# rx.net
KiCad netlist of a schematic drawn in EAGLE
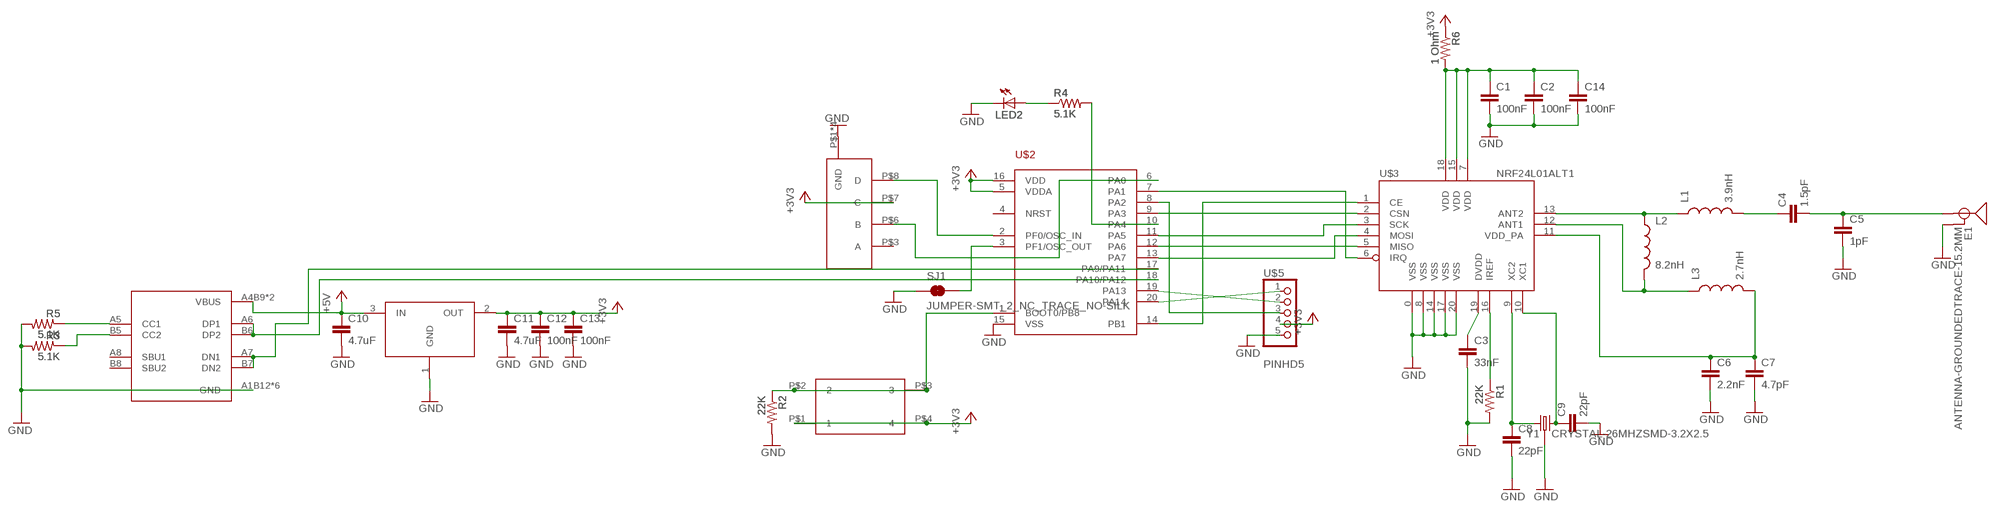
[diagram p0: schematic, sheet 1]

(export (version "E")
  (design (tool "Eeschema 10.0.6"))
  (components
    (comp (ref "C1")
      (value "100nF")
      (footprint "eagle-import:0805")
      (libsource (lib "eagle-import") (part "CAP0805"))
    )
    (comp (ref "C2")
      (value "100nF")
      (footprint "eagle-import:0805")
      (libsource (lib "eagle-import") (part "CAP0805"))
    )
    (comp (ref "C3")
      (value "33nF")
      (footprint "eagle-import:0805")
      (libsource (lib "eagle-import") (part "CAP0805"))
    )
    (comp (ref "C4")
      (value "1.5pF")
      (footprint "eagle-import:0805")
      (libsource (lib "eagle-import") (part "CAP0805"))
    )
    (comp (ref "C5")
      (value "1pF")
      (footprint "eagle-import:0805")
      (libsource (lib "eagle-import") (part "CAP0805"))
    )
    (comp (ref "C6")
      (value "2.2nF")
      (footprint "eagle-import:0805")
      (libsource (lib "eagle-import") (part "CAP0805"))
    )
    (comp (ref "C7")
      (value "4.7pF")
      (footprint "eagle-import:0805")
      (libsource (lib "eagle-import") (part "CAP0805"))
    )
    (comp (ref "C8")
      (value "22pF")
      (footprint "eagle-import:0805")
      (libsource (lib "eagle-import") (part "CAP0805"))
    )
    (comp (ref "C9")
      (value "22pF")
      (footprint "eagle-import:0805")
      (libsource (lib "eagle-import") (part "CAP0805"))
    )
    (comp (ref "C10")
      (value "4.7uF")
      (footprint "eagle-import:0805")
      (libsource (lib "eagle-import") (part "CAP0805"))
    )
    (comp (ref "C11")
      (value "4.7uF")
      (footprint "eagle-import:0805")
      (libsource (lib "eagle-import") (part "CAP0805"))
    )
    (comp (ref "C12")
      (value "100nF")
      (footprint "eagle-import:0805")
      (libsource (lib "eagle-import") (part "CAP0805"))
    )
    (comp (ref "C13")
      (value "100nF")
      (footprint "eagle-import:0805")
      (libsource (lib "eagle-import") (part "CAP0805"))
    )
    (comp (ref "C14")
      (value "100nF")
      (footprint "eagle-import:0805")
      (libsource (lib "eagle-import") (part "CAP0805"))
    )
    (comp (ref "E1")
      (value "ANTENNA-GROUNDEDTRACE-15.2MM")
      (footprint "eagle-import:TRACE_ANTENNA_2.4GHZ_15.2MM")
      (libsource (lib "eagle-import") (part "ANTENNA-GROUNDEDTRACE-15.2MM"))
    )
    (comp (ref "L1")
      (value "3.9nH")
      (footprint "eagle-import:0805")
      (libsource (lib "eagle-import") (part "INDUCTOR0805"))
    )
    (comp (ref "L2")
      (value "8.2nH")
      (footprint "eagle-import:0805")
      (libsource (lib "eagle-import") (part "INDUCTOR0805"))
    )
    (comp (ref "L3")
      (value "2.7nH")
      (footprint "eagle-import:0805")
      (libsource (lib "eagle-import") (part "INDUCTOR0805"))
    )
    (comp (ref "LED2")
      (value "LEDCHIP-LED0805")
      (footprint "eagle-import:CHIP-LED0805")
      (libsource (lib "eagle-import") (part "LEDCHIP-LED0805"))
    )
    (comp (ref "R1")
      (value "22K")
      (footprint "eagle-import:0805")
      (libsource (lib "eagle-import") (part "RESISTOR0805-RES"))
    )
    (comp (ref "R2")
      (value "22K")
      (footprint "eagle-import:0805")
      (libsource (lib "eagle-import") (part "RESISTOR0805-RES"))
    )
    (comp (ref "R3")
      (value "5.1K")
      (footprint "eagle-import:0805")
      (libsource (lib "eagle-import") (part "RESISTOR0805-RES"))
    )
    (comp (ref "R4")
      (value "5.1K")
      (footprint "eagle-import:0805")
      (libsource (lib "eagle-import") (part "RESISTOR0805-RES"))
    )
    (comp (ref "R5")
      (value "5.1K")
      (footprint "eagle-import:0805")
      (libsource (lib "eagle-import") (part "RESISTOR0805-RES"))
    )
    (comp (ref "R6")
      (value "1 Ohm")
      (footprint "eagle-import:0805")
      (libsource (lib "eagle-import") (part "RESISTOR0805-RES"))
    )
    (comp (ref "SJ1")
      (value "JUMPER-SMT_2_NC_TRACE_NO-SILK")
      (footprint "eagle-import:SMT-JUMPER_2_NC_TRACE_NO-SILK")
      (libsource (lib "eagle-import") (part "JUMPER-SMT_2_NC_TRACE_NO-SILK"))
    )
    (comp (ref "U$1")
      (value "SW_3POS_DEVSW_3POS_OFFICIAL")
      (footprint "eagle-import:SW_3POS_FOOT_OFFICIAL")
      (libsource (lib "eagle-import") (part "SW_3POS_DEVSW_3POS_OFFICIAL"))
    )
    (comp (ref "U$2")
      (value "STM32F042F4")
      (footprint "eagle-import:TSSOP20")
      (libsource (lib "eagle-import") (part "STM32F042F4"))
    )
    (comp (ref "U$3")
      (value "NRF24L01ALT1")
      (footprint "eagle-import:QFN20_ALT1")
      (libsource (lib "eagle-import") (part "NRF24L01ALT1"))
    )
    (comp (ref "U$4")
      (value "XC6206_DEV")
      (footprint "eagle-import:SOT23R_INFINEON")
      (libsource (lib "eagle-import") (part "XC6206_DEV"))
    )
    (comp (ref "U$5")
      (value "PINHD5")
      (footprint "eagle-import:1X05")
      (libsource (lib "eagle-import") (part "PINHD5"))
    )
    (comp (ref "U$6")
      (value "USBC_16P")
      (footprint "eagle-import:USBC_16P_FOOT")
      (libsource (lib "eagle-import") (part "USBC_16P"))
    )
    (comp (ref "U$10")
      (value "324_SW324_SWITCH_FOOT_HOLE")
      (footprint "eagle-import:342_SWICH_FOOT_HOLE")
      (libsource (lib "eagle-import") (part "324_SW324_SWITCH_FOOT_HOLE"))
    )
    (comp (ref "Y1")
      (value "CRYSTAL-26MHZSMD-3.2X2.5")
      (footprint "eagle-import:CRYSTAL-SMD-3.2X2.5MM")
      (libsource (lib "eagle-import") (part "CRYSTAL-26MHZSMD-3.2X2.5"))
    )
  )
  (nets
    (net (code "1") (name "+3V3") (class "Default")
      (node (ref "C11") (pin "1") (pinfunction "1_1") (pintype "passive"))
      (node (ref "C12") (pin "1") (pinfunction "1_1") (pintype "passive"))
      (node (ref "C13") (pin "1") (pinfunction "1_1") (pintype "passive"))
      (node (ref "R6") (pin "1") (pinfunction "1_1") (pintype "passive"))
      (node (ref "U$1") (pin "P$7") (pinfunction "C_P$7") (pintype "bidirectional"))
      (node (ref "U$10") (pin "P$1") (pinfunction "1_P$1") (pintype "bidirectional"))
      (node (ref "U$10") (pin "P$4") (pinfunction "4_P$4") (pintype "bidirectional"))
      (node (ref "U$2") (pin "16") (pinfunction "VDD_16") (pintype "bidirectional"))
      (node (ref "U$2") (pin "5") (pinfunction "VDDA_5") (pintype "bidirectional"))
      (node (ref "U$4") (pin "2") (pinfunction "OUT_2") (pintype "bidirectional"))
      (node (ref "U$5") (pin "4") (pinfunction "4_4") (pintype "passive"))
    )
    (net (code "2") (name "+5V") (class "Default")
      (node (ref "C10") (pin "1") (pinfunction "1_1") (pintype "passive"))
      (node (ref "U$4") (pin "3") (pinfunction "IN_3") (pintype "bidirectional"))
      (node (ref "U$6") (pin "A4B9") (pinfunction "VBUS_A4B9") (pintype "bidirectional"))
      (node (ref "U$6") (pin "B4A9") (pinfunction "VBUS_B4A9") (pintype "bidirectional"))
    )
    (net (code "3") (name "GND") (class "Default")
      (node (ref "C1") (pin "2") (pinfunction "2_2") (pintype "passive"))
      (node (ref "C10") (pin "2") (pinfunction "2_2") (pintype "passive"))
      (node (ref "C11") (pin "2") (pinfunction "2_2") (pintype "passive"))
      (node (ref "C12") (pin "2") (pinfunction "2_2") (pintype "passive"))
      (node (ref "C13") (pin "2") (pinfunction "2_2") (pintype "passive"))
      (node (ref "C14") (pin "2") (pinfunction "2_2") (pintype "passive"))
      (node (ref "C2") (pin "2") (pinfunction "2_2") (pintype "passive"))
      (node (ref "C3") (pin "2") (pinfunction "2_2") (pintype "passive"))
      (node (ref "C5") (pin "2") (pinfunction "2_2") (pintype "passive"))
      (node (ref "C6") (pin "2") (pinfunction "2_2") (pintype "passive"))
      (node (ref "C7") (pin "2") (pinfunction "2_2") (pintype "passive"))
      (node (ref "C8") (pin "2") (pinfunction "2_2") (pintype "passive"))
      (node (ref "C9") (pin "2") (pinfunction "2_2") (pintype "passive"))
      (node (ref "E1") (pin "GND") (pinfunction "GND_GND") (pintype "bidirectional"))
      (node (ref "LED2") (pin "C") (pinfunction "C_C") (pintype "passive"))
      (node (ref "R1") (pin "2") (pinfunction "2_2") (pintype "passive"))
      (node (ref "R2") (pin "2") (pinfunction "2_2") (pintype "passive"))
      (node (ref "R3") (pin "2") (pinfunction "2_2") (pintype "passive"))
      (node (ref "R5") (pin "2") (pinfunction "2_2") (pintype "passive"))
      (node (ref "SJ1") (pin "1") (pinfunction "1_1") (pintype "passive"))
      (node (ref "U$1") (pin "P$1") (pinfunction "GND_P$1") (pintype "bidirectional"))
      (node (ref "U$1") (pin "P$2") (pinfunction "GND_P$2") (pintype "bidirectional"))
      (node (ref "U$1") (pin "P$4") (pinfunction "GND_P$4") (pintype "bidirectional"))
      (node (ref "U$1") (pin "P$5") (pinfunction "GND_P$5") (pintype "bidirectional"))
      (node (ref "U$2") (pin "15") (pinfunction "VSS_15") (pintype "bidirectional"))
      (node (ref "U$3") (pin "0") (pinfunction "VSS_0") (pintype "power_in"))
      (node (ref "U$3") (pin "14") (pinfunction "VSS_14") (pintype "power_in"))
      (node (ref "U$3") (pin "17") (pinfunction "VSS_17") (pintype "power_in"))
      (node (ref "U$3") (pin "20") (pinfunction "VSS_20") (pintype "power_in"))
      (node (ref "U$3") (pin "8") (pinfunction "VSS_8") (pintype "power_in"))
      (node (ref "U$4") (pin "1") (pinfunction "GND_1") (pintype "bidirectional"))
      (node (ref "U$5") (pin "5") (pinfunction "5_5") (pintype "passive"))
      (node (ref "U$6") (pin "A1B12") (pinfunction "GND_A1B12") (pintype "bidirectional"))
      (node (ref "U$6") (pin "B11A12") (pinfunction "GND_B11A12") (pintype "bidirectional"))
      (node (ref "U$6") (pin "P$13") (pinfunction "GND_P$13") (pintype "bidirectional"))
      (node (ref "U$6") (pin "P$14") (pinfunction "GND_P$14") (pintype "bidirectional"))
      (node (ref "U$6") (pin "P$15") (pinfunction "GND_P$15") (pintype "bidirectional"))
      (node (ref "U$6") (pin "P$16") (pinfunction "GND_P$16") (pintype "bidirectional"))
      (node (ref "Y1") (pin "2") (pinfunction "3_2") (pintype "passive"))
      (node (ref "Y1") (pin "4") (pinfunction "3_4") (pintype "passive"))
    )
    (net (code "4") (name "Net-(C1-Pad1)") (class "Default")
      (node (ref "C1") (pin "1") (pinfunction "1_1") (pintype "passive"))
      (node (ref "C14") (pin "1") (pinfunction "1_1") (pintype "passive"))
      (node (ref "C2") (pin "1") (pinfunction "1_1") (pintype "passive"))
      (node (ref "R6") (pin "2") (pinfunction "2_2") (pintype "passive"))
      (node (ref "U$3") (pin "15") (pinfunction "VDD_15") (pintype "power_in"))
      (node (ref "U$3") (pin "18") (pinfunction "VDD_18") (pintype "power_in"))
      (node (ref "U$3") (pin "7") (pinfunction "VDD_7") (pintype "power_in"))
    )
    (net (code "5") (name "Net-(C4-Pad1)") (class "Default")
      (node (ref "C4") (pin "1") (pinfunction "1_1") (pintype "passive"))
      (node (ref "L1") (pin "2") (pinfunction "2_2") (pintype "passive"))
    )
    (net (code "6") (name "Net-(E1-SIGNAL)") (class "Default")
      (node (ref "C4") (pin "2") (pinfunction "2_2") (pintype "passive"))
      (node (ref "C5") (pin "1") (pinfunction "1_1") (pintype "passive"))
      (node (ref "E1") (pin "ANT") (pinfunction "SIGNAL_ANT") (pintype "bidirectional"))
    )
    (net (code "7") (name "Net-(LED2-PadA)") (class "Default")
      (node (ref "LED2") (pin "A") (pinfunction "A_A") (pintype "passive"))
      (node (ref "R4") (pin "1") (pinfunction "1_1") (pintype "passive"))
    )
    (net (code "8") (name "Net-(U$1-B)") (class "Default")
      (node (ref "U$1") (pin "P$6") (pinfunction "B_P$6") (pintype "bidirectional"))
      (node (ref "U$2") (pin "6") (pinfunction "PA0_6") (pintype "bidirectional"))
    )
    (net (code "9") (name "Net-(U$1-D)") (class "Default")
      (node (ref "U$1") (pin "P$8") (pinfunction "D_P$8") (pintype "bidirectional"))
      (node (ref "U$2") (pin "2") (pinfunction "PF0/OSC_IN_2") (pintype "bidirectional"))
    )
    (net (code "10") (name "Net-(U$2-PA1)") (class "Default")
      (node (ref "U$2") (pin "7") (pinfunction "PA1_7") (pintype "bidirectional"))
      (node (ref "U$3") (pin "6") (pinfunction "IRQ_6") (pintype "output"))
    )
    (net (code "11") (name "Net-(U$2-PA2)") (class "Default")
      (node (ref "U$2") (pin "8") (pinfunction "PA2_8") (pintype "bidirectional"))
      (node (ref "U$5") (pin "3") (pinfunction "3_3") (pintype "passive"))
    )
    (net (code "12") (name "Net-(U$2-PA3)") (class "Default")
      (node (ref "U$2") (pin "9") (pinfunction "PA3_9") (pintype "bidirectional"))
      (node (ref "U$3") (pin "2") (pinfunction "CSN_2") (pintype "input"))
    )
    (net (code "13") (name "Net-(U$2-PA4)") (class "Default")
      (node (ref "R4") (pin "2") (pinfunction "2_2") (pintype "passive"))
      (node (ref "U$2") (pin "10") (pinfunction "PA4_10") (pintype "bidirectional"))
    )
    (net (code "14") (name "Net-(U$2-PA5)") (class "Default")
      (node (ref "U$2") (pin "11") (pinfunction "PA5_11") (pintype "bidirectional"))
      (node (ref "U$3") (pin "3") (pinfunction "SCK_3") (pintype "input"))
    )
    (net (code "15") (name "Net-(U$2-PA6)") (class "Default")
      (node (ref "U$2") (pin "12") (pinfunction "PA6_12") (pintype "bidirectional"))
      (node (ref "U$3") (pin "5") (pinfunction "MISO_5") (pintype "output"))
    )
    (net (code "16") (name "Net-(U$2-PA7)") (class "Default")
      (node (ref "U$2") (pin "13") (pinfunction "PA7_13") (pintype "bidirectional"))
      (node (ref "U$3") (pin "4") (pinfunction "MOSI_4") (pintype "input"))
    )
    (net (code "17") (name "Net-(U$2-PA9{slash}PA11)") (class "Default")
      (node (ref "U$2") (pin "17") (pinfunction "PA9/PA11_17") (pintype "bidirectional"))
      (node (ref "U$6") (pin "A7") (pinfunction "DN1_A7") (pintype "bidirectional"))
      (node (ref "U$6") (pin "B7") (pinfunction "DN2_B7") (pintype "bidirectional"))
    )
    (net (code "18") (name "Net-(U$2-PA10{slash}PA12)") (class "Default")
      (node (ref "U$2") (pin "18") (pinfunction "PA10/PA12_18") (pintype "bidirectional"))
      (node (ref "U$6") (pin "A6") (pinfunction "DP1_A6") (pintype "bidirectional"))
      (node (ref "U$6") (pin "B6") (pinfunction "DP2_B6") (pintype "bidirectional"))
    )
    (net (code "19") (name "Net-(U$2-PA13)") (class "Default")
      (node (ref "U$2") (pin "19") (pinfunction "PA13_19") (pintype "bidirectional"))
      (node (ref "U$5") (pin "2") (pinfunction "2_2") (pintype "passive"))
    )
    (net (code "20") (name "Net-(U$2-PA14)") (class "Default")
      (node (ref "U$2") (pin "20") (pinfunction "PA14_20") (pintype "bidirectional"))
      (node (ref "U$5") (pin "1") (pinfunction "1_1") (pintype "passive"))
    )
    (net (code "21") (name "Net-(U$2-PB1)") (class "Default")
      (node (ref "U$2") (pin "14") (pinfunction "PB1_14") (pintype "bidirectional"))
      (node (ref "U$3") (pin "1") (pinfunction "CE_1") (pintype "input"))
    )
    (net (code "22") (name "Net-(U$2-PF1{slash}OSC_OUT)") (class "Default")
      (node (ref "SJ1") (pin "2") (pinfunction "2_2") (pintype "passive"))
      (node (ref "U$2") (pin "3") (pinfunction "PF1/OSC_OUT_3") (pintype "bidirectional"))
    )
    (net (code "23") (name "Net-(U$3-ANT1)") (class "Default")
      (node (ref "L2") (pin "2") (pinfunction "2_2") (pintype "passive"))
      (node (ref "L3") (pin "1") (pinfunction "1_1") (pintype "passive"))
      (node (ref "U$3") (pin "12") (pinfunction "ANT1_12") (pintype "output"))
    )
    (net (code "24") (name "Net-(U$3-ANT2)") (class "Default")
      (node (ref "L1") (pin "1") (pinfunction "1_1") (pintype "passive"))
      (node (ref "L2") (pin "1") (pinfunction "1_1") (pintype "passive"))
      (node (ref "U$3") (pin "13") (pinfunction "ANT2_13") (pintype "output"))
    )
    (net (code "25") (name "Net-(U$3-DVDD)") (class "Default")
      (node (ref "C3") (pin "1") (pinfunction "1_1") (pintype "passive"))
      (node (ref "U$3") (pin "19") (pinfunction "DVDD_19") (pintype "power_in"))
    )
    (net (code "26") (name "Net-(U$3-IREF)") (class "Default")
      (node (ref "R1") (pin "1") (pinfunction "1_1") (pintype "passive"))
      (node (ref "U$3") (pin "16") (pinfunction "IREF_16") (pintype "input"))
    )
    (net (code "27") (name "Net-(U$3-VDD_PA)") (class "Default")
      (node (ref "C6") (pin "1") (pinfunction "1_1") (pintype "passive"))
      (node (ref "C7") (pin "1") (pinfunction "1_1") (pintype "passive"))
      (node (ref "L3") (pin "2") (pinfunction "2_2") (pintype "passive"))
      (node (ref "U$3") (pin "11") (pinfunction "VDD_PA_11") (pintype "power_in"))
    )
    (net (code "28") (name "Net-(U$3-XC1)") (class "Default")
      (node (ref "C9") (pin "1") (pinfunction "1_1") (pintype "passive"))
      (node (ref "U$3") (pin "10") (pinfunction "XC1_10") (pintype "input"))
      (node (ref "Y1") (pin "3") (pinfunction "2_3") (pintype "passive"))
    )
    (net (code "29") (name "Net-(U$3-XC2)") (class "Default")
      (node (ref "C8") (pin "1") (pinfunction "1_1") (pintype "passive"))
      (node (ref "U$3") (pin "9") (pinfunction "XC2_9") (pintype "input"))
      (node (ref "Y1") (pin "1") (pinfunction "1_1") (pintype "passive"))
    )
    (net (code "30") (name "Net-(U$6-CC1)") (class "Default")
      (node (ref "R5") (pin "1") (pinfunction "1_1") (pintype "passive"))
      (node (ref "U$6") (pin "A5") (pinfunction "CC1_A5") (pintype "bidirectional"))
    )
    (net (code "31") (name "Net-(U$6-CC2)") (class "Default")
      (node (ref "R3") (pin "1") (pinfunction "1_1") (pintype "passive"))
      (node (ref "U$6") (pin "B5") (pinfunction "CC2_B5") (pintype "bidirectional"))
    )
    (net (code "32") (name "Net-(U$10-2)") (class "Default")
      (node (ref "R2") (pin "1") (pinfunction "1_1") (pintype "passive"))
      (node (ref "U$10") (pin "P$2") (pinfunction "2_P$2") (pintype "bidirectional"))
      (node (ref "U$10") (pin "P$3") (pinfunction "3_P$3") (pintype "bidirectional"))
      (node (ref "U$2") (pin "1") (pinfunction "BOOT0/PB8_1") (pintype "bidirectional"))
    )
    (net (code "33") (name "unconnected-(U$1-A-PadP$3)") (class "Default")
      (node (ref "U$1") (pin "P$3") (pinfunction "A_P$3") (pintype "bidirectional"))
    )
    (net (code "34") (name "unconnected-(U$2-NRST-Pad4)") (class "Default")
      (node (ref "U$2") (pin "4") (pinfunction "NRST_4") (pintype "bidirectional"))
    )
    (net (code "35") (name "unconnected-(U$6-SBU1-PadA8)") (class "Default")
      (node (ref "U$6") (pin "A8") (pinfunction "SBU1_A8") (pintype "bidirectional"))
    )
    (net (code "36") (name "unconnected-(U$6-SBU2-PadB8)") (class "Default")
      (node (ref "U$6") (pin "B8") (pinfunction "SBU2_B8") (pintype "bidirectional"))
    )
  )
)
